# HTC1080_breakout.net
KiCad netlist of a schematic drawn in EAGLE
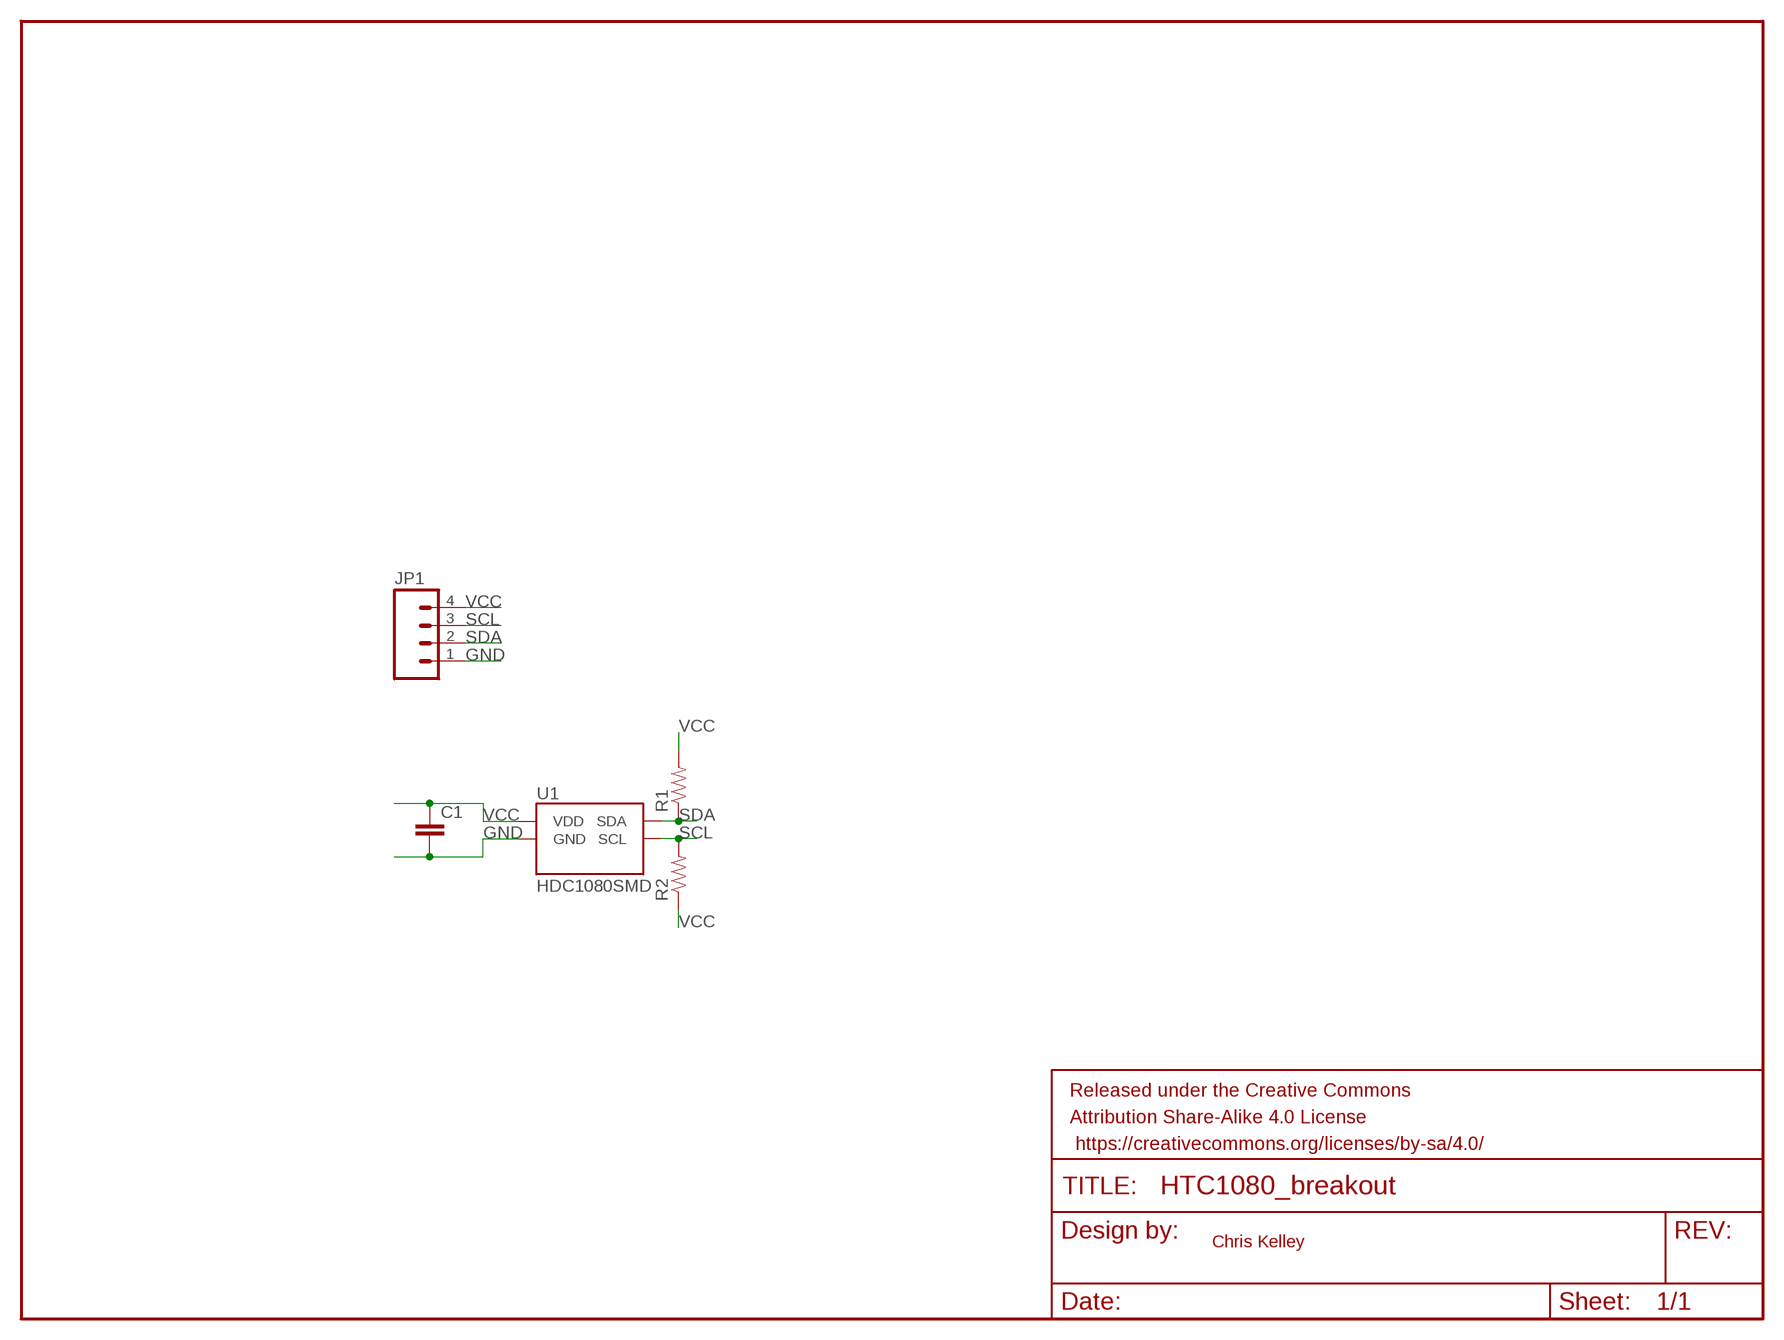
[diagram p0: schematic, sheet 1]

(export (version "E")
  (design (tool "Eeschema 10.0.6"))
  (components
    (comp (ref "C1")
      (value "CAP0603-CAP")
      (footprint "eagle-import:0603-CAP")
      (libsource (lib "eagle-import") (part "CAP0603-CAP"))
    )
    (comp (ref "FRAME1")
      (value "FRAME-LETTER")
      (footprint "eagle-import:CREATIVE_COMMONS")
      (libsource (lib "eagle-import") (part "FRAME-LETTER"))
    )
    (comp (ref "JP1")
      (value "M04PTH")
      (footprint "eagle-import:1X04")
      (libsource (lib "eagle-import") (part "M04PTH"))
    )
    (comp (ref "R1")
      (value "RESISTOR0603-RES")
      (footprint "eagle-import:0603-RES")
      (libsource (lib "eagle-import") (part "RESISTOR0603-RES"))
    )
    (comp (ref "R2")
      (value "RESISTOR0603-RES")
      (footprint "eagle-import:0603-RES")
      (libsource (lib "eagle-import") (part "RESISTOR0603-RES"))
    )
    (comp (ref "U1")
      (value "HDC1080SMD")
      (footprint "eagle-import:TI-PWSON6-DMB")
      (libsource (lib "eagle-import") (part "HDC1080SMD"))
    )
  )
  (nets
    (net (code "1") (name "/GND") (class "Default")
      (node (ref "C1") (pin "2") (pinfunction "2_2") (pintype "passive"))
      (node (ref "JP1") (pin "1") (pinfunction "1_1") (pintype "passive"))
      (node (ref "U1") (pin "GND") (pinfunction "GND_GND") (pintype "power_in"))
    )
    (net (code "2") (name "/SCL") (class "Default")
      (node (ref "JP1") (pin "3") (pinfunction "3_3") (pintype "passive"))
      (node (ref "R2") (pin "2") (pinfunction "2_2") (pintype "passive"))
      (node (ref "U1") (pin "SCL") (pinfunction "SCL_SCL") (pintype "input"))
    )
    (net (code "3") (name "/SDA") (class "Default")
      (node (ref "JP1") (pin "2") (pinfunction "2_2") (pintype "passive"))
      (node (ref "R1") (pin "1") (pinfunction "1_1") (pintype "passive"))
      (node (ref "U1") (pin "SDA") (pinfunction "SDA_SDA") (pintype "bidirectional"))
    )
    (net (code "4") (name "/VCC") (class "Default")
      (node (ref "C1") (pin "1") (pinfunction "1_1") (pintype "passive"))
      (node (ref "JP1") (pin "4") (pinfunction "4_4") (pintype "passive"))
      (node (ref "R1") (pin "2") (pinfunction "2_2") (pintype "passive"))
      (node (ref "R2") (pin "1") (pinfunction "1_1") (pintype "passive"))
      (node (ref "U1") (pin "VDD") (pinfunction "VDD_VDD") (pintype "power_in"))
    )
  )
)
